# Sheet2_1.net
KiCad netlist of a schematic drawn in Altium Designer
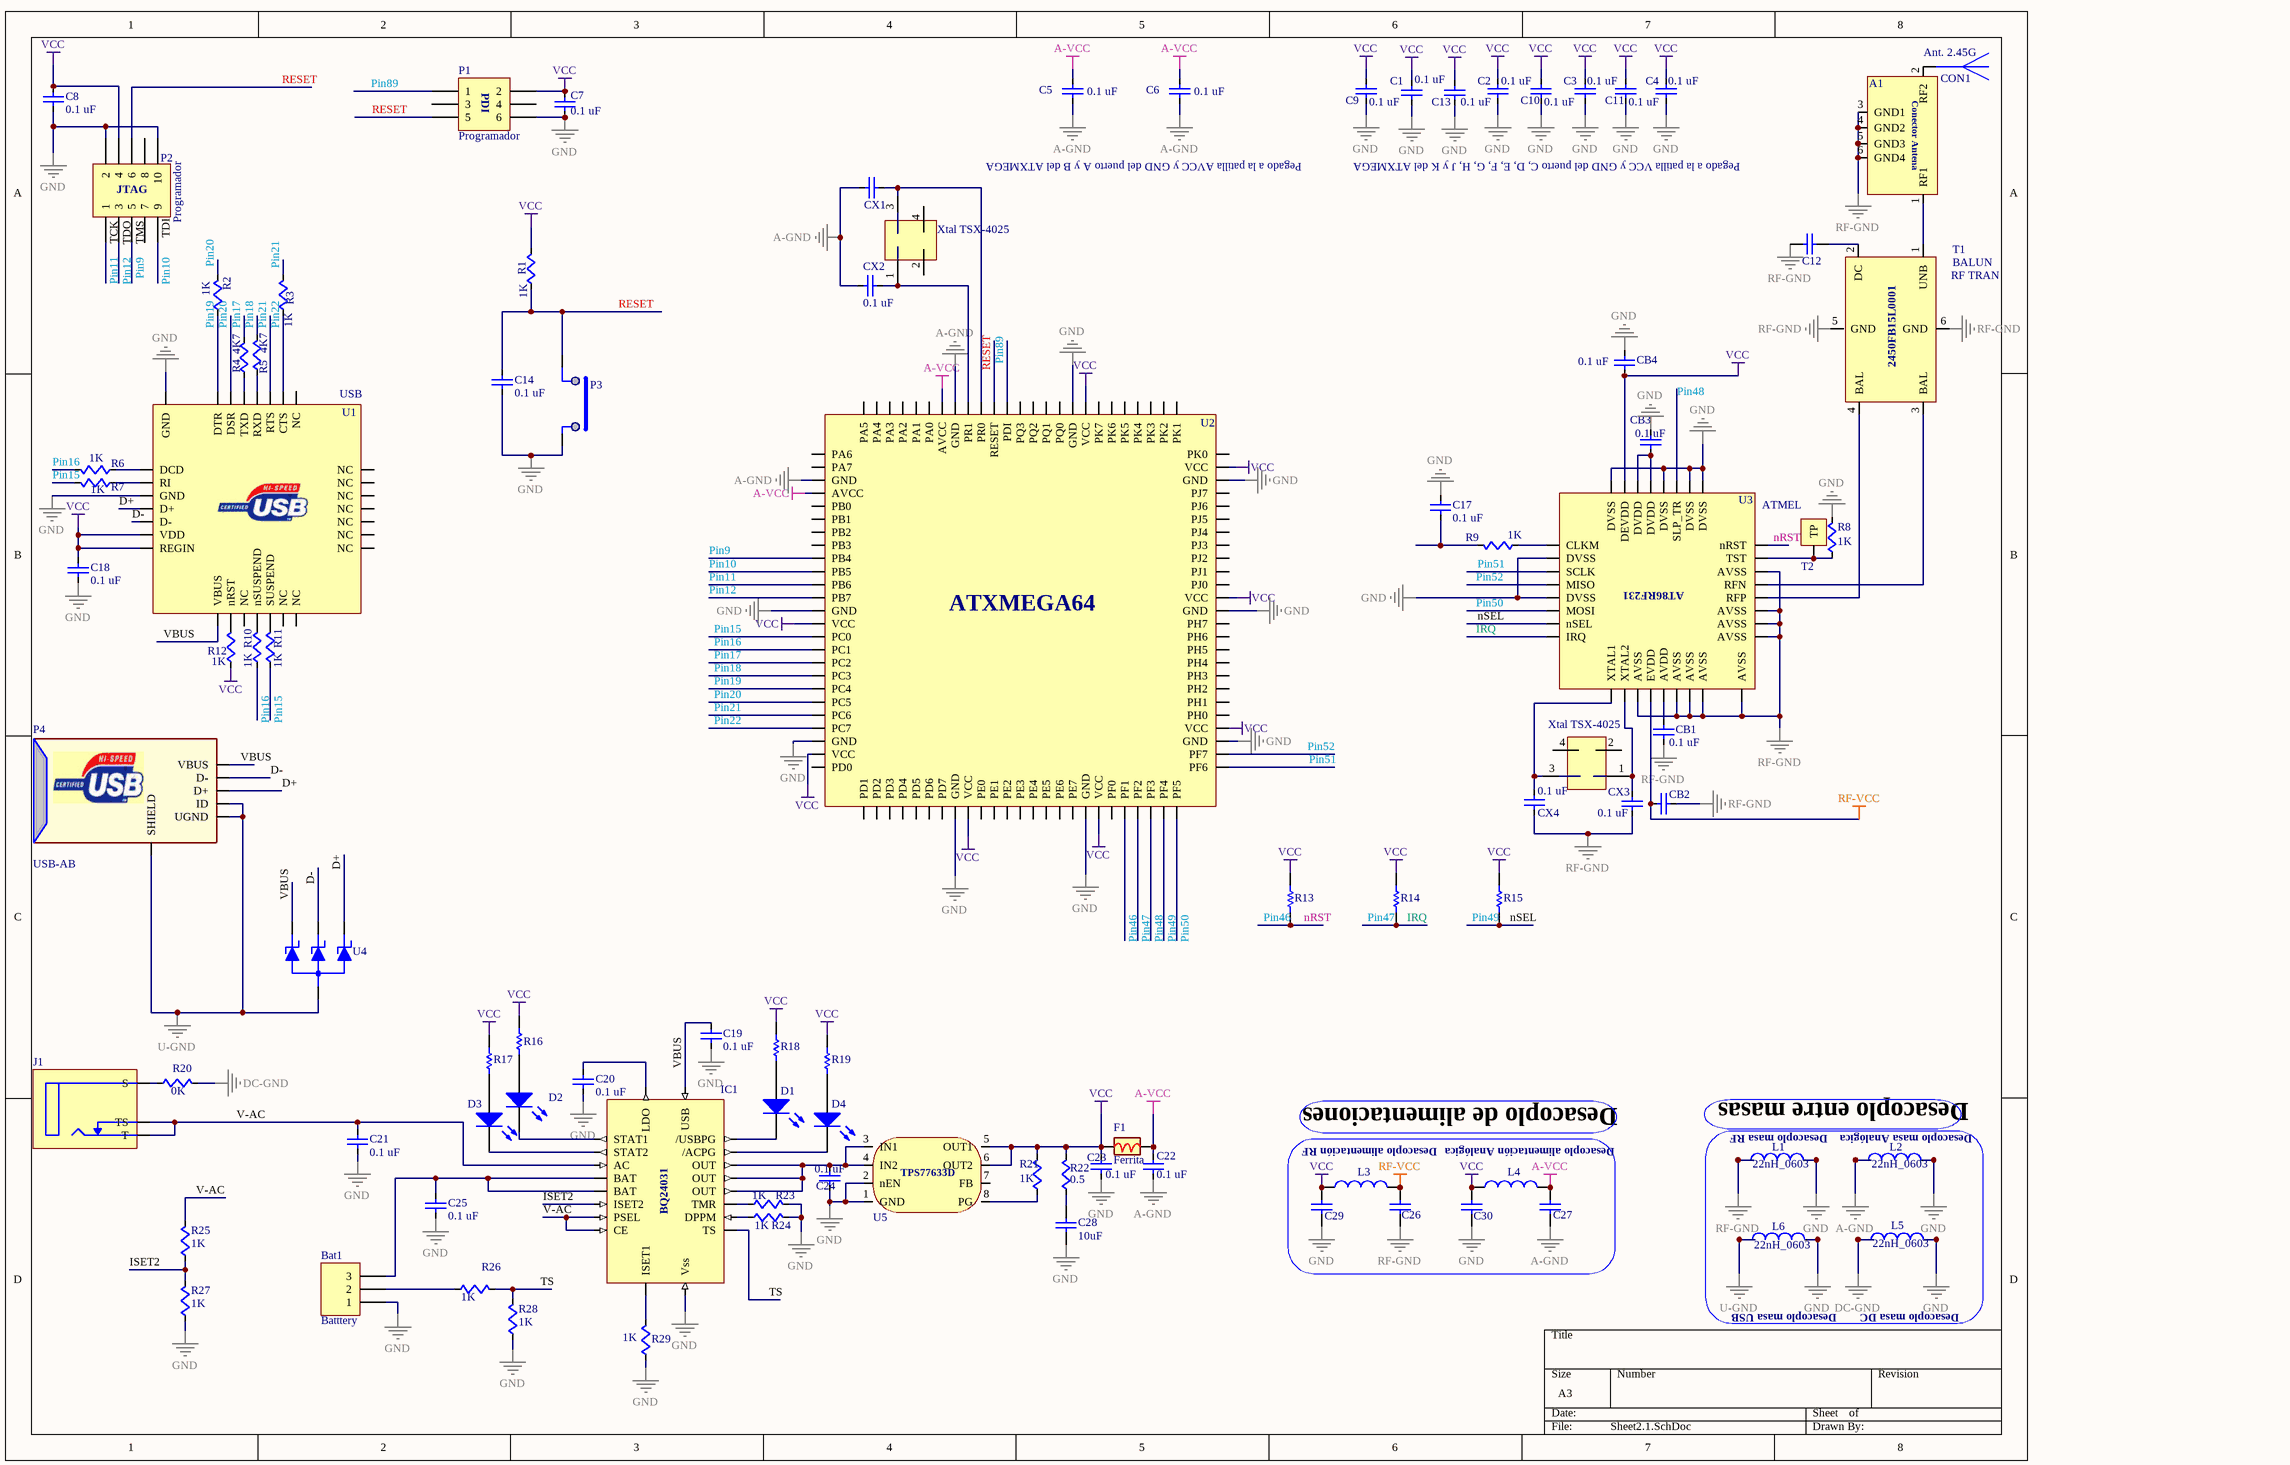
[diagram p0: Sheet2.1.SchDoc]

(export (version "E")
  (design (tool "Eeschema 10.0.6"))
  (components
    (comp (ref "A1")
      (value "Ant. 2.45G")
      (footprint "ANTENNA CHIP")
      (description "ANTENNA CHIP 2.4GHZ")
      (libsource (lib "Mia") (part "2450AT18A100"))
    )
    (comp (ref "Bat1")
      (value "Batttery")
      (footprint "HDR1X3")
      (description "Header, 3-Pin")
      (fields (field (name "PUBLISHER") "Altium Limited"))
      (libsource (lib "Mia") (part "Header 3"))
    )
    (comp (ref "C1")
      (value "C")
      (footprint "0402")
      (description "CONDENSADOR")
      (fields (field (name "VALOR") "0.1 uF"))
      (libsource (lib "Mia") (part "C"))
    )
    (comp (ref "C2")
      (value "C")
      (footprint "0402")
      (description "CONDENSADOR")
      (fields (field (name "VALOR") "0.1 uF"))
      (libsource (lib "Mia") (part "C"))
    )
    (comp (ref "C3")
      (value "C")
      (footprint "0402")
      (description "CONDENSADOR")
      (fields (field (name "VALOR") "0.1 uF"))
      (libsource (lib "Mia") (part "C"))
    )
    (comp (ref "C4")
      (value "C")
      (footprint "0402")
      (description "CONDENSADOR")
      (fields (field (name "VALOR") "0.1 uF"))
      (libsource (lib "Mia") (part "C"))
    )
    (comp (ref "C5")
      (value "C")
      (footprint "0402")
      (description "CONDENSADOR")
      (fields (field (name "VALOR") "0.1 uF"))
      (libsource (lib "Mia") (part "C"))
    )
    (comp (ref "C6")
      (value "C")
      (footprint "0402")
      (description "CONDENSADOR")
      (fields (field (name "VALOR") "0.1 uF"))
      (libsource (lib "Mia") (part "C"))
    )
    (comp (ref "C7")
      (value "C")
      (footprint "0402")
      (description "CONDENSADOR")
      (fields (field (name "VALOR") "0.1 uF"))
      (libsource (lib "Mia") (part "C"))
    )
    (comp (ref "C8")
      (value "C")
      (footprint "0402")
      (description "CONDENSADOR")
      (fields (field (name "VALOR") "0.1 uF"))
      (libsource (lib "Mia") (part "C"))
    )
    (comp (ref "C9")
      (value "C")
      (footprint "0402")
      (description "CONDENSADOR")
      (fields (field (name "VALOR") "0.1 uF"))
      (libsource (lib "Mia") (part "C"))
    )
    (comp (ref "C10")
      (value "C")
      (footprint "0402")
      (description "CONDENSADOR")
      (fields (field (name "VALOR") "0.1 uF"))
      (libsource (lib "Mia") (part "C"))
    )
    (comp (ref "C11")
      (value "C")
      (footprint "0402")
      (description "CONDENSADOR")
      (fields (field (name "VALOR") "0.1 uF"))
      (libsource (lib "Mia") (part "C"))
    )
    (comp (ref "C12")
      (value "22pF_0402")
      (footprint "0402")
      (description "CAP CER 56PF 50V 5% C0G 0402")
      (libsource (lib "Mia") (part "56pF_0402"))
    )
    (comp (ref "C13")
      (value "C")
      (footprint "0402")
      (description "CONDENSADOR")
      (fields (field (name "VALOR") "0.1 uF"))
      (libsource (lib "Mia") (part "C"))
    )
    (comp (ref "C14")
      (value "C")
      (footprint "0402")
      (description "CONDENSADOR")
      (fields (field (name "VALOR") "0.1 uF"))
      (libsource (lib "Mia") (part "C"))
    )
    (comp (ref "C17")
      (value "C")
      (footprint "0402")
      (description "CONDENSADOR")
      (fields (field (name "VALOR") "0.1 uF"))
      (libsource (lib "Mia") (part "C"))
    )
    (comp (ref "C18")
      (value "C")
      (footprint "0402")
      (description "CONDENSADOR")
      (fields (field (name "VALOR") "0.1 uF"))
      (libsource (lib "Mia") (part "C"))
    )
    (comp (ref "C19")
      (value "C")
      (footprint "0402")
      (description "CONDENSADOR")
      (fields (field (name "VALOR") "0.1 uF"))
      (libsource (lib "Mia") (part "C"))
    )
    (comp (ref "C20")
      (value "C")
      (footprint "0402")
      (description "CONDENSADOR")
      (fields (field (name "VALOR") "0.1 uF"))
      (libsource (lib "Mia") (part "C"))
    )
    (comp (ref "C21")
      (value "C")
      (footprint "0402")
      (description "CONDENSADOR")
      (fields (field (name "VALOR") "0.1 uF"))
      (libsource (lib "Mia") (part "C"))
    )
    (comp (ref "C22")
      (value "C")
      (footprint "0402")
      (description "CONDENSADOR")
      (fields (field (name "VALOR") "0.1 uF"))
      (libsource (lib "Mia") (part "C"))
    )
    (comp (ref "C23")
      (value "C")
      (footprint "0402")
      (description "CONDENSADOR")
      (fields (field (name "VALOR") "0.1 uF"))
      (libsource (lib "Mia") (part "C"))
    )
    (comp (ref "C24")
      (value "C")
      (footprint "0402")
      (description "CONDENSADOR")
      (fields (field (name "VALOR") "0.1 uF"))
      (libsource (lib "Mia") (part "C"))
    )
    (comp (ref "C25")
      (value "C")
      (footprint "0402")
      (description "CONDENSADOR")
      (fields (field (name "VALOR") "0.1 uF"))
      (libsource (lib "Mia") (part "C"))
    )
    (comp (ref "C26")
      (value "100nF_0805")
      (footprint "0805")
      (description "CAP CER 100PF 630V X7R 0805")
      (libsource (lib "Mia") (part "100nF_0805"))
    )
    (comp (ref "C27")
      (value "100nF_0805")
      (footprint "0805")
      (description "CAP CER 100PF 630V X7R 0805")
      (libsource (lib "Mia") (part "100nF_0805"))
    )
    (comp (ref "C28")
      (value "10uF")
      (footprint "0805")
      (description "CAP CER 10UF 10V Y5V 0805")
      (libsource (lib "Mia") (part "10uF_0805"))
    )
    (comp (ref "C29")
      (value "100nF_0805")
      (footprint "0805")
      (description "CAP CER 100PF 630V X7R 0805")
      (libsource (lib "Mia") (part "100nF_0805"))
    )
    (comp (ref "C30")
      (value "100nF_0805")
      (footprint "0805")
      (description "CAP CER 100PF 630V X7R 0805")
      (libsource (lib "Mia") (part "100nF_0805"))
    )
    (comp (ref "CB1")
      (value "C")
      (footprint "0402")
      (description "CONDENSADOR")
      (fields (field (name "VALOR") "0.1 uF"))
      (libsource (lib "Mia") (part "C"))
    )
    (comp (ref "CB2")
      (value "C")
      (footprint "0402")
      (description "CONDENSADOR")
      (fields (field (name "VALOR") "0.1 uF"))
      (libsource (lib "Mia") (part "C"))
    )
    (comp (ref "CB3")
      (value "C")
      (footprint "0402")
      (description "CONDENSADOR")
      (fields (field (name "VALOR") "0.1 uF"))
      (libsource (lib "Mia") (part "C"))
    )
    (comp (ref "CB4")
      (value "C")
      (footprint "0402")
      (description "CONDENSADOR")
      (fields (field (name "VALOR") "0.1 uF"))
      (libsource (lib "Mia") (part "C"))
    )
    (comp (ref "CON1")
      (value "Conector Antena")
      (footprint "MM8430-2600_Coaxial Connectors")
      (description "CONN MW COAXIAL WITH SWITCH")
      (libsource (lib "Mia") (part "CON ANT-MM8430-2600RA1"))
    )
    (comp (ref "CX1")
      (value "C")
      (footprint "0402")
      (description "CONDENSADOR")
      (libsource (lib "Mia") (part "C"))
    )
    (comp (ref "CX2")
      (value "C")
      (footprint "0402")
      (description "CONDENSADOR")
      (fields (field (name "VALOR") "0.1 uF"))
      (libsource (lib "Mia") (part "C"))
    )
    (comp (ref "CX3")
      (value "C")
      (footprint "0402")
      (description "CONDENSADOR")
      (fields (field (name "VALOR") "0.1 uF"))
      (libsource (lib "Mia") (part "C"))
    )
    (comp (ref "CX4")
      (value "C")
      (footprint "0402")
      (description "CONDENSADOR")
      (libsource (lib "Mia") (part "C"))
    )
    (comp (ref "D1")
      (value "Diodo Led")
      (footprint "Diode Led")
      (description "Typical INFRARED GaAs LED")
      (libsource (lib "Mia") (part "LTST-C230CKT"))
    )
    (comp (ref "D2")
      (value "Diodo Led")
      (footprint "Diode Led")
      (description "Typical INFRARED GaAs LED")
      (libsource (lib "Mia") (part "LTST-C230CKT"))
    )
    (comp (ref "D3")
      (value "Diodo Led")
      (footprint "Diode Led")
      (description "Typical INFRARED GaAs LED")
      (libsource (lib "Mia") (part "LTST-C230CKT"))
    )
    (comp (ref "D4")
      (value "Diodo Led")
      (footprint "Diode Led")
      (description "Typical INFRARED GaAs LED")
      (libsource (lib "Mia") (part "LTST-C230CKT"))
    )
    (comp (ref "F1")
      (value "Ferrita")
      (footprint "0603")
      (description "Chip Ferrite Beads")
      (libsource (lib "Mia") (part "BLM21AH102SN1"))
    )
    (comp (ref "IC1")
      (value "BQ24031")
      (footprint "BQ24031")
      (description "IC PWR MANAGEMENT SYSTEM 20-QFN")
      (libsource (lib "Mia") (part "BQ24031"))
    )
    (comp (ref "J1")
      (value "CAMSHOT")
      (footprint "MJ-2509N")
      (description "CONN MONO JACK 2.5MM PCB MNT")
      (libsource (lib "*") (part "MJ-2509N_1"))
    )
    (comp (ref "L1")
      (value "22nH_0603")
      (footprint "0603")
      (description "CER INDUCTOR 22NH 0603")
      (libsource (lib "Mia") (part "22nH_0603"))
    )
    (comp (ref "L2")
      (value "22nH_0603")
      (footprint "0603")
      (description "CER INDUCTOR 22NH 0603")
      (libsource (lib "Mia") (part "22nH_0603"))
    )
    (comp (ref "L3")
      (value "22nH_0603")
      (footprint "0603")
      (description "CER INDUCTOR 22NH 0603")
      (libsource (lib "Mia") (part "22nH_0603"))
    )
    (comp (ref "L4")
      (value "22nH_0603")
      (footprint "0603")
      (description "CER INDUCTOR 22NH 0603")
      (libsource (lib "Mia") (part "22nH_0603"))
    )
    (comp (ref "L5")
      (value "22nH_0603")
      (footprint "0603")
      (description "CER INDUCTOR 22NH 0603")
      (libsource (lib "Mia") (part "22nH_0603"))
    )
    (comp (ref "L6")
      (value "22nH_0603")
      (footprint "0603")
      (description "CER INDUCTOR 22NH 0603")
      (libsource (lib "Mia") (part "22nH_0603"))
    )
    (comp (ref "P1")
      (value "Programador")
      (footprint "HDR2X3")
      (description "Header, 3-Pin, Dual row")
      (fields (field (name "PUBLISHER") "Altium Limited"))
      (libsource (lib "Mia") (part "Header 3X2"))
    )
    (comp (ref "P2")
      (value "Programador")
      (footprint "HDR2X5")
      (description "Header, 5-Pin, Dual row")
      (fields (field (name "PUBLISHER") "Altium Limited"))
      (libsource (lib "Mia") (part "Header 5X2"))
    )
    (comp (ref "P3")
      (value "Pulsador")
      (footprint "PUSH-BUTTON-W")
      (description "SWITCH TACT 6X3.5MM H=4.3MM 180G")
      (libsource (lib "Mia") (part "PUSHBUTTON"))
    )
    (comp (ref "P4")
      (value "USB-AB")
      (footprint "USB-MINI-AB-SMT")
      (description "CONN RECEPT USB 5POS RT ANG SMD")
      (libsource (lib "Mia") (part "WM1722"))
    )
    (comp (ref "R1")
      (value "1K")
      (footprint "0603")
      (description "RESISTENCIA 0402 SMD")
      (fields (field (name "Comment") "R 0402"))
      (libsource (lib "Mia") (part "R 0402"))
    )
    (comp (ref "R2")
      (value "1K")
      (footprint "0603")
      (description "RESISTENCIA 0402 SMD")
      (fields (field (name "Comment") "R 0402"))
      (libsource (lib "Mia") (part "R 0402"))
    )
    (comp (ref "R3")
      (value "1K")
      (footprint "0603")
      (description "RESISTENCIA 0402 SMD")
      (fields (field (name "Comment") "R 0402"))
      (libsource (lib "Mia") (part "R 0402"))
    )
    (comp (ref "R4")
      (value "4K7")
      (footprint "0603")
      (description "RESISTENCIA 0402 SMD")
      (fields (field (name "Comment") "R 0402"))
      (libsource (lib "Mia") (part "R 0402"))
    )
    (comp (ref "R5")
      (value "4K7")
      (footprint "0603")
      (description "RESISTENCIA 0402 SMD")
      (fields (field (name "Comment") "R 0402"))
      (libsource (lib "Mia") (part "R 0402"))
    )
    (comp (ref "R6")
      (value "1K")
      (footprint "0603")
      (description "RESISTENCIA 0402 SMD")
      (fields (field (name "Comment") "R 0402"))
      (libsource (lib "Mia") (part "R 0402"))
    )
    (comp (ref "R7")
      (value "1K")
      (footprint "0603")
      (description "RESISTENCIA 0402 SMD")
      (fields (field (name "Comment") "R 0402"))
      (libsource (lib "Mia") (part "R 0402"))
    )
    (comp (ref "R8")
      (value "1K")
      (footprint "0603")
      (description "RESISTENCIA 0402 SMD")
      (fields (field (name "Comment") "R 0402"))
      (libsource (lib "Mia") (part "R 0402"))
    )
    (comp (ref "R9")
      (value "1K")
      (footprint "0603")
      (description "RESISTENCIA 0402 SMD")
      (fields (field (name "Comment") "R 0402"))
      (libsource (lib "Mia") (part "R 0402"))
    )
    (comp (ref "R10")
      (value "1K")
      (footprint "0603")
      (description "RESISTENCIA 0402 SMD")
      (fields (field (name "Comment") "R 0402"))
      (libsource (lib "Mia") (part "R 0402"))
    )
    (comp (ref "R11")
      (value "1K")
      (footprint "0603")
      (description "RESISTENCIA 0402 SMD")
      (fields (field (name "Comment") "R 0402"))
      (libsource (lib "Mia") (part "R 0402"))
    )
    (comp (ref "R12")
      (value "1K")
      (footprint "0603")
      (description "RESISTENCIA 0402 SMD")
      (fields (field (name "Comment") "R 0402"))
      (libsource (lib "Mia") (part "R 0402"))
    )
    (comp (ref "R13")
      (value "16.9kohm-0805")
      (footprint "0805")
      (description "RES 16.9K OHM 1/8W 1% 0805 SMD")
      (libsource (lib "Mia") (part "16.9kohm-0805"))
    )
    (comp (ref "R14")
      (value "16.9kohm-0805")
      (footprint "0805")
      (description "RES 16.9K OHM 1/8W 1% 0805 SMD")
      (libsource (lib "Mia") (part "16.9kohm-0805"))
    )
    (comp (ref "R15")
      (value "16.9kohm-0805")
      (footprint "0805")
      (description "RES 16.9K OHM 1/8W 1% 0805 SMD")
      (libsource (lib "Mia") (part "16.9kohm-0805"))
    )
    (comp (ref "R16")
      (value "16.9kohm-0805")
      (footprint "0805")
      (description "RES 16.9K OHM 1/8W 1% 0805 SMD")
      (libsource (lib "Mia") (part "16.9kohm-0805"))
    )
    (comp (ref "R17")
      (value "16.9kohm-0805")
      (footprint "0805")
      (description "RES 16.9K OHM 1/8W 1% 0805 SMD")
      (libsource (lib "Mia") (part "16.9kohm-0805"))
    )
    (comp (ref "R18")
      (value "16.9kohm-0805")
      (footprint "0805")
      (description "RES 16.9K OHM 1/8W 1% 0805 SMD")
      (libsource (lib "Mia") (part "16.9kohm-0805"))
    )
    (comp (ref "R19")
      (value "16.9kohm-0805")
      (footprint "0805")
      (description "RES 16.9K OHM 1/8W 1% 0805 SMD")
      (libsource (lib "Mia") (part "16.9kohm-0805"))
    )
    (comp (ref "R20")
      (value "0K")
      (footprint "0603")
      (description "RESISTENCIA 0402 SMD")
      (fields (field (name "Comment") "R 0402"))
      (libsource (lib "Mia") (part "R 0402"))
    )
    (comp (ref "R21")
      (value "1K")
      (footprint "0603")
      (description "RESISTENCIA 0402 SMD")
      (fields (field (name "Comment") "R 0402"))
      (libsource (lib "Mia") (part "R 0402"))
    )
    (comp (ref "R22")
      (value "0.5")
      (footprint "0603")
      (description "RESISTENCIA 0402 SMD")
      (fields (field (name "Comment") "R 0402"))
      (libsource (lib "Mia") (part "R 0402"))
    )
    (comp (ref "R23")
      (value "1K")
      (footprint "0603")
      (description "RESISTENCIA 0402 SMD")
      (fields (field (name "Comment") "R 0402"))
      (libsource (lib "Mia") (part "R 0402"))
    )
    (comp (ref "R24")
      (value "1K")
      (footprint "0603")
      (description "RESISTENCIA 0402 SMD")
      (fields (field (name "Comment") "R 0402"))
      (libsource (lib "Mia") (part "R 0402"))
    )
    (comp (ref "R25")
      (value "1K")
      (footprint "0603")
      (description "RESISTENCIA 0402 SMD")
      (fields (field (name "Comment") "R 0402"))
      (libsource (lib "Mia") (part "R 0402"))
    )
    (comp (ref "R26")
      (value "1K")
      (footprint "0603")
      (description "RESISTENCIA 0402 SMD")
      (fields (field (name "Comment") "R 0402"))
      (libsource (lib "Mia") (part "R 0402"))
    )
    (comp (ref "R27")
      (value "1K")
      (footprint "0603")
      (description "RESISTENCIA 0402 SMD")
      (fields (field (name "Comment") "R 0402"))
      (libsource (lib "Mia") (part "R 0402"))
    )
    (comp (ref "R28")
      (value "1K")
      (footprint "0603")
      (description "RESISTENCIA 0402 SMD")
      (fields (field (name "Comment") "R 0402"))
      (libsource (lib "Mia") (part "R 0402"))
    )
    (comp (ref "R29")
      (value "1K")
      (footprint "0603")
      (description "RESISTENCIA 0402 SMD")
      (fields (field (name "Comment") "R 0402"))
      (libsource (lib "Mia") (part "R 0402"))
    )
    (comp (ref "T1")
      (value "BALUN")
      (footprint "BALUN")
      (description "FILTER BALUN CER CHIP 2.4GHZ")
      (libsource (lib "Mia") (part "2450FB39B100E"))
    )
    (comp (ref "T2")
      (value "TESTPOINT")
      (footprint "TESTPOINT")
      (description "Punto de Test")
      (libsource (lib "Mia") (part "TESTPOINT"))
    )
    (comp (ref "U1")
      (value "USB")
      (footprint "QFN28_5X5")
      (description "IC USB-TO-UART BRIDGE 28MLP")
      (libsource (lib "Mia") (part "CP2102"))
    )
    (comp (ref "U2")
      (value "XMEGA")
      (footprint "Quad100")
      (description "MCU AVR 64K FLASH 1.6V 100-TQFP")
      (libsource (lib "Mia") (part "ATXMEGA64A1"))
    )
    (comp (ref "U3")
      (value "RF TRAN")
      (footprint "QFN32_50")
      (description "IC TXRX ZIGBEE/802.15.4 32QFN")
      (fields (field (name "FABRICANTE") "ATMEL"))
      (libsource (lib "Mia") (part "AT86RF231"))
    )
    (comp (ref "U4")
      (value "TVS")
      (footprint "SOT-143")
      (description "TVS AVAL DIODE ARRAY 3 CH SOT143")
      (libsource (lib "Mia") (part "SP0503BAHTG"))
    )
    (comp (ref "U5")
      (value "TPS77633D")
      (footprint "TPS77633D")
      (description "IC 3.3V 500MA LDO REG 8-SOIC")
      (libsource (lib "Mia") (part "TPS77633D"))
    )
    (comp (ref "Xtal1")
      (value "Xtal TSX-4025")
      (footprint "TSX-4025")
      (description "Cristal 16Mhz")
      (libsource (lib "Mia") (part "Xtal TSX-4025"))
    )
    (comp (ref "Xtal2")
      (value "Xtal TSX-4025")
      (footprint "TSX-4025")
      (description "Cristal 16Mhz")
      (libsource (lib "") (part "Xtal TSX-4025_1"))
    )
  )
  (nets
    (net (code "1") (name "/D+") (class "Default")
      (node (ref "P4") (pin "D+") (pinfunction "D+_D+") (pintype "passive"))
      (node (ref "U1") (pin "4") (pinfunction "D+_4") (pintype "passive"))
      (node (ref "U4") (pin "2") (pinfunction "C_2") (pintype "passive"))
    )
    (net (code "2") (name "/D-") (class "Default")
      (node (ref "P4") (pin "D-") (pinfunction "D-_D-") (pintype "passive"))
      (node (ref "U1") (pin "5") (pinfunction "D-_5") (pintype "passive"))
      (node (ref "U4") (pin "3") (pinfunction "C_3") (pintype "passive"))
    )
    (net (code "3") (name "/IRQ") (class "Default")
      (node (ref "R14") (pin "1") (pinfunction "1_1") (pintype "passive"))
      (node (ref "U2") (pin "47") (pinfunction "PF2_47") (pintype "passive"))
      (node (ref "U3") (pin "24") (pinfunction "IRQ_24") (pintype "passive"))
    )
    (net (code "4") (name "/ISET2") (class "Default")
      (node (ref "IC1") (pin "7") (pinfunction "ISET2_7") (pintype "input"))
      (node (ref "R25") (pin "1") (pinfunction "1_1") (pintype "passive"))
      (node (ref "R27") (pin "2") (pinfunction "2_2") (pintype "passive"))
    )
    (net (code "5") (name "/Pin9") (class "Default")
      (node (ref "P2") (pin "5") (pinfunction "5_5") (pintype "passive"))
      (node (ref "U2") (pin "9") (pinfunction "PB4_9") (pintype "passive"))
    )
    (net (code "6") (name "/Pin10") (class "Default")
      (node (ref "P2") (pin "9") (pinfunction "9_9") (pintype "passive"))
      (node (ref "U2") (pin "10") (pinfunction "PB5_10") (pintype "passive"))
    )
    (net (code "7") (name "/Pin11") (class "Default")
      (node (ref "P2") (pin "1") (pinfunction "1_1") (pintype "passive"))
      (node (ref "U2") (pin "11") (pinfunction "PB6_11") (pintype "passive"))
    )
    (net (code "8") (name "/Pin12") (class "Default")
      (node (ref "P2") (pin "3") (pinfunction "3_3") (pintype "passive"))
      (node (ref "U2") (pin "12") (pinfunction "PB7_12") (pintype "passive"))
    )
    (net (code "9") (name "/Pin15") (class "Default")
      (node (ref "R11") (pin "1") (pinfunction "1_1") (pintype "passive"))
      (node (ref "R7") (pin "2") (pinfunction "2_2") (pintype "passive"))
      (node (ref "U2") (pin "15") (pinfunction "PC0_15") (pintype "passive"))
    )
    (net (code "10") (name "/Pin16") (class "Default")
      (node (ref "R10") (pin "1") (pinfunction "1_1") (pintype "passive"))
      (node (ref "R6") (pin "2") (pinfunction "2_2") (pintype "passive"))
      (node (ref "U2") (pin "16") (pinfunction "PC1_16") (pintype "passive"))
    )
    (net (code "11") (name "/Pin17") (class "Default")
      (node (ref "R4") (pin "2") (pinfunction "2_2") (pintype "passive"))
      (node (ref "U2") (pin "17") (pinfunction "PC2_17") (pintype "passive"))
    )
    (net (code "12") (name "/Pin18") (class "Default")
      (node (ref "R5") (pin "2") (pinfunction "2_2") (pintype "passive"))
      (node (ref "U2") (pin "18") (pinfunction "PC3_18") (pintype "passive"))
    )
    (net (code "13") (name "/Pin19") (class "Default")
      (node (ref "R2") (pin "1") (pinfunction "1_1") (pintype "passive"))
      (node (ref "U1") (pin "28") (pinfunction "DTR_28") (pintype "passive"))
      (node (ref "U2") (pin "19") (pinfunction "PC4_19") (pintype "passive"))
    )
    (net (code "14") (name "/Pin20") (class "Default")
      (node (ref "R2") (pin "2") (pinfunction "2_2") (pintype "passive"))
      (node (ref "U1") (pin "27") (pinfunction "DSR_27") (pintype "passive"))
      (node (ref "U2") (pin "20") (pinfunction "PC5_20") (pintype "passive"))
    )
    (net (code "15") (name "/Pin21") (class "Default")
      (node (ref "R3") (pin "2") (pinfunction "2_2") (pintype "passive"))
      (node (ref "U1") (pin "24") (pinfunction "RTS_24") (pintype "passive"))
      (node (ref "U2") (pin "21") (pinfunction "PC6_21") (pintype "passive"))
    )
    (net (code "16") (name "/Pin22") (class "Default")
      (node (ref "R3") (pin "1") (pinfunction "1_1") (pintype "passive"))
      (node (ref "U1") (pin "23") (pinfunction "CTS_23") (pintype "passive"))
      (node (ref "U2") (pin "22") (pinfunction "PC7_22") (pintype "passive"))
    )
    (net (code "17") (name "/Pin46") (class "Default")
      (node (ref "R13") (pin "1") (pinfunction "1_1") (pintype "passive"))
      (node (ref "U2") (pin "46") (pinfunction "PF1_46") (pintype "passive"))
      (node (ref "U3") (pin "8") (pinfunction "nRST_8") (pintype "passive"))
    )
    (net (code "18") (name "/Pin48") (class "Default")
      (node (ref "U2") (pin "48") (pinfunction "PF3_48") (pintype "passive"))
      (node (ref "U3") (pin "11") (pinfunction "SLP_TR_11") (pintype "passive"))
    )
    (net (code "19") (name "/Pin49") (class "Default")
      (node (ref "R15") (pin "1") (pinfunction "1_1") (pintype "passive"))
      (node (ref "U2") (pin "49") (pinfunction "PF4_49") (pintype "passive"))
      (node (ref "U3") (pin "23") (pinfunction "nSEL_23") (pintype "passive"))
    )
    (net (code "20") (name "/Pin50") (class "Default")
      (node (ref "U2") (pin "50") (pinfunction "PF5_50") (pintype "passive"))
      (node (ref "U3") (pin "22") (pinfunction "MOSI_22") (pintype "passive"))
    )
    (net (code "21") (name "/Pin51") (class "Default")
      (node (ref "U2") (pin "51") (pinfunction "PF6_51") (pintype "passive"))
      (node (ref "U3") (pin "19") (pinfunction "SCLK_19") (pintype "passive"))
    )
    (net (code "22") (name "/Pin52") (class "Default")
      (node (ref "U2") (pin "52") (pinfunction "PF7_52") (pintype "passive"))
      (node (ref "U3") (pin "20") (pinfunction "MISO_20") (pintype "passive"))
    )
    (net (code "23") (name "/Pin89") (class "Default")
      (node (ref "P1") (pin "1") (pinfunction "1_1") (pintype "passive"))
      (node (ref "U2") (pin "89") (pinfunction "PDI_89") (pintype "passive"))
    )
    (net (code "24") (name "/RESET") (class "Default")
      (node (ref "C14") (pin "1") (pinfunction "1_1") (pintype "passive"))
      (node (ref "P1") (pin "5") (pinfunction "5_5") (pintype "passive"))
      (node (ref "P2") (pin "6") (pinfunction "6_6") (pintype "passive"))
      (node (ref "P3") (pin "1") (pinfunction "1_1") (pintype "passive"))
      (node (ref "R1") (pin "1") (pinfunction "1_1") (pintype "passive"))
      (node (ref "U2") (pin "90") (pinfunction "RESET_90") (pintype "passive"))
    )
    (net (code "29") (name "/TS") (class "Default")
      (node (ref "IC1") (pin "12") (pinfunction "TS_12") (pintype "bidirectional"))
      (node (ref "R26") (pin "2") (pinfunction "2_2") (pintype "passive"))
      (node (ref "R28") (pin "2") (pinfunction "2_2") (pintype "passive"))
    )
    (net (code "30") (name "/V-AC") (class "Default")
      (node (ref "C21") (pin "1") (pinfunction "1_1") (pintype "passive"))
      (node (ref "IC1") (pin "4") (pinfunction "AC_4") (pintype "input"))
      (node (ref "IC1") (pin "8") (pinfunction "PSEL_8") (pintype "input"))
      (node (ref "IC1") (pin "9") (pinfunction "CE_9") (pintype "input"))
      (node (ref "J1") (pin "2") (pinfunction "T_2") (pintype "passive"))
      (node (ref "J1") (pin "3") (pinfunction "TS_3") (pintype "passive"))
      (node (ref "R25") (pin "2") (pinfunction "2_2") (pintype "passive"))
    )
    (net (code "31") (name "/VBUS") (class "Default")
      (node (ref "C19") (pin "1") (pinfunction "1_1") (pintype "passive"))
      (node (ref "IC1") (pin "20") (pinfunction "USB_20") (pintype "input"))
      (node (ref "P4") (pin "VBUS") (pinfunction "VBUS_VBUS") (pintype "passive"))
      (node (ref "U1") (pin "8") (pinfunction "VBUS_8") (pintype "passive"))
      (node (ref "U4") (pin "4") (pinfunction "C_4") (pintype "passive"))
    )
    (net (code "32") (name "A-GND") (class "Default")
      (node (ref "C22") (pin "2") (pinfunction "2_2") (pintype "passive"))
      (node (ref "C27") (pin "1") (pinfunction "1_1") (pintype "passive"))
      (node (ref "C5") (pin "2") (pinfunction "2_2") (pintype "passive"))
      (node (ref "C6") (pin "2") (pinfunction "2_2") (pintype "passive"))
      (node (ref "CX1") (pin "1") (pinfunction "1_1") (pintype "passive"))
      (node (ref "CX2") (pin "1") (pinfunction "1_1") (pintype "passive"))
      (node (ref "L2") (pin "1") (pinfunction "1_1") (pintype "passive"))
      (node (ref "U2") (pin "3") (pinfunction "GND_3") (pintype "passive"))
      (node (ref "U2") (pin "93") (pinfunction "GND_93") (pintype "passive"))
    )
    (net (code "33") (name "A-VCC") (class "Default")
      (node (ref "C22") (pin "1") (pinfunction "1_1") (pintype "passive"))
      (node (ref "C27") (pin "2") (pinfunction "2_2") (pintype "passive"))
      (node (ref "C5") (pin "1") (pinfunction "1_1") (pintype "passive"))
      (node (ref "C6") (pin "1") (pinfunction "1_1") (pintype "passive"))
      (node (ref "F1") (pin "2") (pinfunction "Y_2") (pintype "passive"))
      (node (ref "L4") (pin "2") (pinfunction "2_2") (pintype "passive"))
      (node (ref "U2") (pin "4") (pinfunction "AVCC_4") (pintype "passive"))
      (node (ref "U2") (pin "94") (pinfunction "AVCC_94") (pintype "passive"))
    )
    (net (code "34") (name "DC-GND") (class "Default")
      (node (ref "L5") (pin "1") (pinfunction "1_1") (pintype "passive"))
      (node (ref "R20") (pin "2") (pinfunction "2_2") (pintype "passive"))
    )
    (net (code "35") (name "GND") (class "Default")
      (node (ref "Bat1") (pin "1") (pinfunction "1_1") (pintype "passive"))
      (node (ref "C1") (pin "2") (pinfunction "2_2") (pintype "passive"))
      (node (ref "C10") (pin "2") (pinfunction "2_2") (pintype "passive"))
      (node (ref "C11") (pin "2") (pinfunction "2_2") (pintype "passive"))
      (node (ref "C13") (pin "2") (pinfunction "2_2") (pintype "passive"))
      (node (ref "C14") (pin "2") (pinfunction "2_2") (pintype "passive"))
      (node (ref "C17") (pin "1") (pinfunction "1_1") (pintype "passive"))
      (node (ref "C18") (pin "2") (pinfunction "2_2") (pintype "passive"))
      (node (ref "C19") (pin "2") (pinfunction "2_2") (pintype "passive"))
      (node (ref "C2") (pin "2") (pinfunction "2_2") (pintype "passive"))
      (node (ref "C20") (pin "2") (pinfunction "2_2") (pintype "passive"))
      (node (ref "C21") (pin "2") (pinfunction "2_2") (pintype "passive"))
      (node (ref "C23") (pin "2") (pinfunction "2_2") (pintype "passive"))
      (node (ref "C24") (pin "2") (pinfunction "2_2") (pintype "passive"))
      (node (ref "C25") (pin "2") (pinfunction "2_2") (pintype "passive"))
      (node (ref "C28") (pin "1") (pinfunction "1_1") (pintype "passive"))
      (node (ref "C29") (pin "1") (pinfunction "1_1") (pintype "passive"))
      (node (ref "C3") (pin "2") (pinfunction "2_2") (pintype "passive"))
      (node (ref "C30") (pin "1") (pinfunction "1_1") (pintype "passive"))
      (node (ref "C4") (pin "2") (pinfunction "2_2") (pintype "passive"))
      (node (ref "C7") (pin "2") (pinfunction "2_2") (pintype "passive"))
      (node (ref "C8") (pin "2") (pinfunction "2_2") (pintype "passive"))
      (node (ref "C9") (pin "2") (pinfunction "2_2") (pintype "passive"))
      (node (ref "CB3") (pin "1") (pinfunction "1_1") (pintype "passive"))
      (node (ref "CB4") (pin "2") (pinfunction "2_2") (pintype "passive"))
      (node (ref "IC1") (pin "11") (pinfunction "Vss_11") (pintype "input"))
      (node (ref "L1") (pin "2") (pinfunction "2_2") (pintype "passive"))
      (node (ref "L2") (pin "2") (pinfunction "2_2") (pintype "passive"))
      (node (ref "L5") (pin "2") (pinfunction "2_2") (pintype "passive"))
      (node (ref "L6") (pin "2") (pinfunction "2_2") (pintype "passive"))
      (node (ref "P1") (pin "6") (pinfunction "6_6") (pintype "passive"))
      (node (ref "P2") (pin "10") (pinfunction "10_10") (pintype "passive"))
      (node (ref "P2") (pin "2") (pinfunction "2_2") (pintype "passive"))
      (node (ref "P3") (pin "2") (pinfunction "2_2") (pintype "passive"))
      (node (ref "R23") (pin "2") (pinfunction "2_2") (pintype "passive"))
      (node (ref "R24") (pin "2") (pinfunction "2_2") (pintype "passive"))
      (node (ref "R27") (pin "1") (pinfunction "1_1") (pintype "passive"))
      (node (ref "R28") (pin "1") (pinfunction "1_1") (pintype "passive"))
      (node (ref "R29") (pin "1") (pinfunction "1_1") (pintype "passive"))
      (node (ref "R8") (pin "2") (pinfunction "2_2") (pintype "passive"))
      (node (ref "U1") (pin "0") (pinfunction "GND_0") (pintype "passive"))
      (node (ref "U1") (pin "3") (pinfunction "GND_3") (pintype "passive"))
      (node (ref "U2") (pin "13") (pinfunction "GND_13") (pintype "passive"))
      (node (ref "U2") (pin "23") (pinfunction "GND_23") (pintype "passive"))
      (node (ref "U2") (pin "33") (pinfunction "GND_33") (pintype "passive"))
      (node (ref "U2") (pin "43") (pinfunction "GND_43") (pintype "passive"))
      (node (ref "U2") (pin "53") (pinfunction "GND_53") (pintype "passive"))
      (node (ref "U2") (pin "63") (pinfunction "GND_63") (pintype "passive"))
      (node (ref "U2") (pin "73") (pinfunction "GND_73") (pintype "passive"))
      (node (ref "U2") (pin "84") (pinfunction "GND_84") (pintype "passive"))
      (node (ref "U3") (pin "10") (pinfunction "DVSS_10") (pintype "passive"))
      (node (ref "U3") (pin "12") (pinfunction "DVSS_12") (pintype "passive"))
      (node (ref "U3") (pin "16") (pinfunction "DVSS_16") (pintype "passive"))
      (node (ref "U3") (pin "18") (pinfunction "DVSS_18") (pintype "passive"))
      (node (ref "U3") (pin "21") (pinfunction "DVSS_21") (pintype "passive"))
      (node (ref "U3") (pin "9") (pinfunction "DVSS_9") (pintype "passive"))
      (node (ref "U5") (pin "1") (pinfunction "GND_1") (pintype "passive"))
      (node (ref "U5") (pin "2") (pinfunction "nEN_2") (pintype "passive"))
    )
    (net (code "36") (name "Net-(A1-OUT)") (class "Default")
      (node (ref "A1") (pin "1") (pinfunction "OUT_1") (pintype "passive"))
      (node (ref "CON1") (pin "2") (pinfunction "RF2_2") (pintype "passive"))
    )
    (net (code "37") (name "Net-(Bat1-Pad2)") (class "Default")
      (node (ref "Bat1") (pin "2") (pinfunction "2_2") (pintype "passive"))
      (node (ref "R26") (pin "1") (pinfunction "1_1") (pintype "passive"))
    )
    (net (code "38") (name "Net-(Bat1-Pad3)") (class "Default")
      (node (ref "Bat1") (pin "3") (pinfunction "3_3") (pintype "passive"))
      (node (ref "C25") (pin "1") (pinfunction "1_1") (pintype "passive"))
      (node (ref "IC1") (pin "5") (pinfunction "BAT_5") (pintype "bidirectional"))
      (node (ref "IC1") (pin "6") (pinfunction "BAT_6") (pintype "bidirectional"))
    )
    (net (code "39") (name "Net-(C17-Pad2)") (class "Default")
      (node (ref "C17") (pin "2") (pinfunction "2_2") (pintype "passive"))
      (node (ref "R9") (pin "2") (pinfunction "2_2") (pintype "passive"))
    )
    (net (code "40") (name "Net-(C28-Pad2)") (class "Default")
      (node (ref "C28") (pin "2") (pinfunction "2_2") (pintype "passive"))
      (node (ref "R22") (pin "1") (pinfunction "1_1") (pintype "passive"))
    )
    (net (code "41") (name "Net-(CB3-Pad2)") (class "Default")
      (node (ref "CB3") (pin "2") (pinfunction "2_2") (pintype "passive"))
      (node (ref "U3") (pin "13") (pinfunction "DVDD_13") (pintype "passive"))
      (node (ref "U3") (pin "14") (pinfunction "DVDD_14") (pintype "passive"))
    )
    (net (code "42") (name "Net-(CON1-RF1)") (class "Default")
      (node (ref "CON1") (pin "1") (pinfunction "RF1_1") (pintype "passive"))
      (node (ref "T1") (pin "1") (pinfunction "UNB_1") (pintype "passive"))
    )
    (net (code "43") (name "Net-(D1-A)") (class "Default")
      (node (ref "D1") (pin "1") (pinfunction "A_1") (pintype "passive"))
      (node (ref "R18") (pin "1") (pinfunction "1_1") (pintype "passive"))
    )
    (net (code "44") (name "Net-(D1-K)") (class "Default")
      (node (ref "D1") (pin "2") (pinfunction "K_2") (pintype "passive"))
      (node (ref "IC1") (pin "19") (pinfunction "/USBPG_19") (pintype "output"))
    )
    (net (code "45") (name "Net-(D2-A)") (class "Default")
      (node (ref "D2") (pin "1") (pinfunction "A_1") (pintype "passive"))
      (node (ref "R16") (pin "1") (pinfunction "1_1") (pintype "passive"))
    )
    (net (code "46") (name "Net-(D2-K)") (class "Default")
      (node (ref "D2") (pin "2") (pinfunction "K_2") (pintype "passive"))
      (node (ref "IC1") (pin "2") (pinfunction "STAT1_2") (pintype "output"))
    )
    (net (code "47") (name "Net-(D3-A)") (class "Default")
      (node (ref "D3") (pin "1") (pinfunction "A_1") (pintype "passive"))
      (node (ref "R17") (pin "1") (pinfunction "1_1") (pintype "passive"))
    )
    (net (code "48") (name "Net-(D3-K)") (class "Default")
      (node (ref "D3") (pin "2") (pinfunction "K_2") (pintype "passive"))
      (node (ref "IC1") (pin "3") (pinfunction "STAT2_3") (pintype "output"))
    )
    (net (code "49") (name "Net-(D4-A)") (class "Default")
      (node (ref "D4") (pin "1") (pinfunction "A_1") (pintype "passive"))
      (node (ref "R19") (pin "1") (pinfunction "1_1") (pintype "passive"))
    )
    (net (code "50") (name "Net-(D4-K)") (class "Default")
      (node (ref "D4") (pin "2") (pinfunction "K_2") (pintype "passive"))
      (node (ref "IC1") (pin "18") (pinfunction "/ACPG_18") (pintype "output"))
    )
    (net (code "51") (name "Net-(IC1-DPPM)") (class "Default")
      (node (ref "IC1") (pin "13") (pinfunction "DPPM_13") (pintype "input"))
      (node (ref "R23") (pin "1") (pinfunction "1_1") (pintype "passive"))
    )
    (net (code "52") (name "Net-(IC1-ISET1)") (class "Default")
      (node (ref "IC1") (pin "10") (pinfunction "ISET1_10") (pintype "bidirectional"))
      (node (ref "R29") (pin "2") (pinfunction "2_2") (pintype "passive"))
    )
    (net (code "53") (name "Net-(IC1-LDO)") (class "Default")
      (node (ref "C20") (pin "1") (pinfunction "1_1") (pintype "passive"))
      (node (ref "IC1") (pin "1") (pinfunction "LDO_1") (pintype "output"))
    )
    (net (code "54") (name "Net-(IC1-TMR)") (class "Default")
      (node (ref "IC1") (pin "14") (pinfunction "TMR_14") (pintype "bidirectional"))
      (node (ref "R24") (pin "1") (pinfunction "1_1") (pintype "passive"))
    )
    (net (code "55") (name "Net-(J1-S)") (class "Default")
      (node (ref "J1") (pin "1") (pinfunction "S_1") (pintype "passive"))
      (node (ref "R20") (pin "1") (pinfunction "1_1") (pintype "passive"))
    )
    (net (code "56") (name "Net-(T1-DC)") (class "Default")
      (node (ref "C12") (pin "2") (pinfunction "2_2") (pintype "passive"))
      (node (ref "T1") (pin "2") (pinfunction "DC_2") (pintype "passive"))
    )
    (net (code "57") (name "Net-(T2-TP)") (class "Default")
      (node (ref "R8") (pin "1") (pinfunction "1_1") (pintype "passive"))
      (node (ref "T2") (pin "1") (pinfunction "TP_1") (pintype "passive"))
      (node (ref "U3") (pin "7") (pinfunction "TST_7") (pintype "passive"))
    )
    (net (code "58") (name "Net-(U1-DCD)") (class "Default")
      (node (ref "R6") (pin "1") (pinfunction "1_1") (pintype "passive"))
      (node (ref "U1") (pin "1") (pinfunction "DCD_1") (pintype "passive"))
    )
    (net (code "59") (name "Net-(U1-RI)") (class "Default")
      (node (ref "R7") (pin "1") (pinfunction "1_1") (pintype "passive"))
      (node (ref "U1") (pin "2") (pinfunction "RI_2") (pintype "passive"))
    )
    (net (code "60") (name "Net-(U1-RXD)") (class "Default")
      (node (ref "R5") (pin "1") (pinfunction "1_1") (pintype "passive"))
      (node (ref "U1") (pin "25") (pinfunction "RXD_25") (pintype "passive"))
    )
    (net (code "61") (name "Net-(U1-SUSPEND)") (class "Default")
      (node (ref "R11") (pin "2") (pinfunction "2_2") (pintype "passive"))
      (node (ref "U1") (pin "12") (pinfunction "SUSPEND_12") (pintype "passive"))
    )
    (net (code "62") (name "Net-(U1-TXD)") (class "Default")
      (node (ref "R4") (pin "1") (pinfunction "1_1") (pintype "passive"))
      (node (ref "U1") (pin "26") (pinfunction "TXD_26") (pintype "passive"))
    )
    (net (code "63") (name "Net-(U1-nRST)") (class "Default")
      (node (ref "R12") (pin "2") (pinfunction "2_2") (pintype "passive"))
      (node (ref "U1") (pin "9") (pinfunction "nRST_9") (pintype "passive"))
    )
    (net (code "64") (name "Net-(U1-nSUSPEND)") (class "Default")
      (node (ref "R10") (pin "2") (pinfunction "2_2") (pintype "passive"))
      (node (ref "U1") (pin "11") (pinfunction "nSUSPEND_11") (pintype "passive"))
    )
    (net (code "65") (name "Net-(U2-PR0)") (class "Default")
      (node (ref "CX1") (pin "2") (pinfunction "2_2") (pintype "passive"))
      (node (ref "U2") (pin "91") (pinfunction "PR0_91") (pintype "passive"))
      (node (ref "Xtal1") (pin "3") (pinfunction "OSC2_3") (pintype "passive"))
    )
    (net (code "66") (name "Net-(U2-PR1)") (class "Default")
      (node (ref "CX2") (pin "2") (pinfunction "2_2") (pintype "passive"))
      (node (ref "U2") (pin "92") (pinfunction "PR1_92") (pintype "passive"))
      (node (ref "Xtal1") (pin "1") (pinfunction "OSC1_1") (pintype "passive"))
    )
    (net (code "67") (name "Net-(U3-AVDD)") (class "Default")
      (node (ref "CB1") (pin "2") (pinfunction "2_2") (pintype "passive"))
      (node (ref "U3") (pin "29") (pinfunction "AVDD_29") (pintype "passive"))
    )
    (net (code "68") (name "Net-(U3-CLKM)") (class "Default")
      (node (ref "R9") (pin "1") (pinfunction "1_1") (pintype "passive"))
      (node (ref "U3") (pin "17") (pinfunction "CLKM_17") (pintype "passive"))
    )
    (net (code "69") (name "Net-(U3-RFN)") (class "Default")
      (node (ref "T1") (pin "3") (pinfunction "BAL_3") (pintype "passive"))
      (node (ref "U3") (pin "5") (pinfunction "RFN_5") (pintype "passive"))
    )
    (net (code "70") (name "Net-(U3-RFP)") (class "Default")
      (node (ref "T1") (pin "4") (pinfunction "BAL_4") (pintype "passive"))
      (node (ref "U3") (pin "4") (pinfunction "RFP_4") (pintype "passive"))
    )
    (net (code "71") (name "Net-(U3-XTAL1)") (class "Default")
      (node (ref "CX4") (pin "2") (pinfunction "2_2") (pintype "passive"))
      (node (ref "U3") (pin "25") (pinfunction "XTAL1_25") (pintype "passive"))
      (node (ref "Xtal2") (pin "3") (pinfunction "OSC2_3") (pintype "passive"))
    )
    (net (code "72") (name "Net-(U3-XTAL2)") (class "Default")
      (node (ref "CX3") (pin "2") (pinfunction "2_2") (pintype "passive"))
      (node (ref "U3") (pin "26") (pinfunction "XTAL2_26") (pintype "passive"))
      (node (ref "Xtal2") (pin "1") (pinfunction "OSC1_1") (pintype "passive"))
    )
    (net (code "73") (name "Net-(U5-IN1)") (class "Default")
      (node (ref "C24") (pin "1") (pinfunction "1_1") (pintype "passive"))
      (node (ref "IC1") (pin "15") (pinfunction "OUT_15") (pintype "output"))
      (node (ref "IC1") (pin "16") (pinfunction "OUT_16") (pintype "output"))
      (node (ref "IC1") (pin "17") (pinfunction "OUT_17") (pintype "output"))
      (node (ref "U5") (pin "3") (pinfunction "IN1_3") (pintype "passive"))
      (node (ref "U5") (pin "4") (pinfunction "IN2_4") (pintype "passive"))
    )
    (net (code "74") (name "Net-(U5-PG)") (class "Default")
      (node (ref "R21") (pin "1") (pinfunction "1_1") (pintype "passive"))
      (node (ref "U5") (pin "8") (pinfunction "PG_8") (pintype "passive"))
    )
    (net (code "75") (name "RF-GND") (class "Default")
      (node (ref "C12") (pin "1") (pinfunction "1_1") (pintype "passive"))
      (node (ref "C26") (pin "1") (pinfunction "1_1") (pintype "passive"))
      (node (ref "CB1") (pin "1") (pinfunction "1_1") (pintype "passive"))
      (node (ref "CB2") (pin "1") (pinfunction "1_1") (pintype "passive"))
      (node (ref "CON1") (pin "3") (pinfunction "GND1_3") (pintype "passive"))
      (node (ref "CON1") (pin "4") (pinfunction "GND2_4") (pintype "passive"))
      (node (ref "CON1") (pin "5") (pinfunction "GND3_5") (pintype "passive"))
      (node (ref "CON1") (pin "6") (pinfunction "GND4_6") (pintype "passive"))
      (node (ref "CX3") (pin "1") (pinfunction "1_1") (pintype "passive"))
      (node (ref "CX4") (pin "1") (pinfunction "1_1") (pintype "passive"))
      (node (ref "L1") (pin "1") (pinfunction "1_1") (pintype "passive"))
      (node (ref "T1") (pin "5") (pinfunction "GND_5") (pintype "passive"))
      (node (ref "T1") (pin "6") (pinfunction "GND_6") (pintype "passive"))
      (node (ref "U3") (pin "1") (pinfunction "AVSS_1") (pintype "passive"))
      (node (ref "U3") (pin "2") (pinfunction "AVSS_2") (pintype "passive"))
      (node (ref "U3") (pin "27") (pinfunction "AVSS_27") (pintype "passive"))
      (node (ref "U3") (pin "3") (pinfunction "AVSS_3") (pintype "passive"))
      (node (ref "U3") (pin "30") (pinfunction "AVSS_30") (pintype "passive"))
      (node (ref "U3") (pin "31") (pinfunction "AVSS_31") (pintype "passive"))
      (node (ref "U3") (pin "32") (pinfunction "AVSS_32") (pintype "passive"))
      (node (ref "U3") (pin "33") (pinfunction "AVSS_33") (pintype "passive"))
      (node (ref "U3") (pin "6") (pinfunction "AVSS_6") (pintype "passive"))
    )
    (net (code "76") (name "RF-VCC") (class "Default")
      (node (ref "C26") (pin "2") (pinfunction "2_2") (pintype "passive"))
      (node (ref "CB2") (pin "2") (pinfunction "2_2") (pintype "passive"))
      (node (ref "L3") (pin "2") (pinfunction "2_2") (pintype "passive"))
      (node (ref "U3") (pin "28") (pinfunction "EVDD_28") (pintype "passive"))
    )
    (net (code "77") (name "U-GND") (class "Default")
      (node (ref "L6") (pin "1") (pinfunction "1_1") (pintype "passive"))
      (node (ref "P4") (pin "ID") (pinfunction "ID_ID") (pintype "passive"))
      (node (ref "P4") (pin "SHIELD") (pinfunction "SHIELD_SHIELD") (pintype "passive"))
      (node (ref "P4") (pin "UGND") (pinfunction "UGND_UGND") (pintype "passive"))
      (node (ref "U4") (pin "1") (pinfunction "GND_1") (pintype "passive"))
    )
    (net (code "78") (name "VCC") (class "Default")
      (node (ref "C1") (pin "1") (pinfunction "1_1") (pintype "passive"))
      (node (ref "C10") (pin "1") (pinfunction "1_1") (pintype "passive"))
      (node (ref "C11") (pin "1") (pinfunction "1_1") (pintype "passive"))
      (node (ref "C13") (pin "1") (pinfunction "1_1") (pintype "passive"))
      (node (ref "C18") (pin "1") (pinfunction "1_1") (pintype "passive"))
      (node (ref "C2") (pin "1") (pinfunction "1_1") (pintype "passive"))
      (node (ref "C23") (pin "1") (pinfunction "1_1") (pintype "passive"))
      (node (ref "C29") (pin "2") (pinfunction "2_2") (pintype "passive"))
      (node (ref "C3") (pin "1") (pinfunction "1_1") (pintype "passive"))
      (node (ref "C30") (pin "2") (pinfunction "2_2") (pintype "passive"))
      (node (ref "C4") (pin "1") (pinfunction "1_1") (pintype "passive"))
      (node (ref "C7") (pin "1") (pinfunction "1_1") (pintype "passive"))
      (node (ref "C8") (pin "1") (pinfunction "1_1") (pintype "passive"))
      (node (ref "C9") (pin "1") (pinfunction "1_1") (pintype "passive"))
      (node (ref "CB4") (pin "1") (pinfunction "1_1") (pintype "passive"))
      (node (ref "F1") (pin "1") (pinfunction "X_1") (pintype "passive"))
      (node (ref "L3") (pin "1") (pinfunction "1_1") (pintype "passive"))
      (node (ref "L4") (pin "1") (pinfunction "1_1") (pintype "passive"))
      (node (ref "P1") (pin "2") (pinfunction "2_2") (pintype "passive"))
      (node (ref "P2") (pin "4") (pinfunction "4_4") (pintype "passive"))
      (node (ref "R1") (pin "2") (pinfunction "2_2") (pintype "passive"))
      (node (ref "R12") (pin "1") (pinfunction "1_1") (pintype "passive"))
      (node (ref "R13") (pin "2") (pinfunction "2_2") (pintype "passive"))
      (node (ref "R14") (pin "2") (pinfunction "2_2") (pintype "passive"))
      (node (ref "R15") (pin "2") (pinfunction "2_2") (pintype "passive"))
      (node (ref "R16") (pin "2") (pinfunction "2_2") (pintype "passive"))
      (node (ref "R17") (pin "2") (pinfunction "2_2") (pintype "passive"))
      (node (ref "R18") (pin "2") (pinfunction "2_2") (pintype "passive"))
      (node (ref "R19") (pin "2") (pinfunction "2_2") (pintype "passive"))
      (node (ref "R21") (pin "2") (pinfunction "2_2") (pintype "passive"))
      (node (ref "R22") (pin "2") (pinfunction "2_2") (pintype "passive"))
      (node (ref "U1") (pin "6") (pinfunction "VDD_6") (pintype "passive"))
      (node (ref "U1") (pin "7") (pinfunction "REGIN_7") (pintype "passive"))
      (node (ref "U2") (pin "14") (pinfunction "VCC_14") (pintype "passive"))
      (node (ref "U2") (pin "24") (pinfunction "VCC_24") (pintype "passive"))
      (node (ref "U2") (pin "34") (pinfunction "VCC_34") (pintype "passive"))
      (node (ref "U2") (pin "44") (pinfunction "VCC_44") (pintype "passive"))
      (node (ref "U2") (pin "54") (pinfunction "VCC_54") (pintype "passive"))
      (node (ref "U2") (pin "64") (pinfunction "VCC_64") (pintype "passive"))
      (node (ref "U2") (pin "74") (pinfunction "VCC_74") (pintype "passive"))
      (node (ref "U2") (pin "83") (pinfunction "VCC_83") (pintype "passive"))
      (node (ref "U3") (pin "15") (pinfunction "DEVDD_15") (pintype "passive"))
      (node (ref "U5") (pin "5") (pinfunction "OUT1_5") (pintype "passive"))
      (node (ref "U5") (pin "6") (pinfunction "OUT2_6") (pintype "passive"))
    )
    (net (code "79") (name "unconnected-(P1-Pad3)") (class "Default")
      (node (ref "P1") (pin "3") (pinfunction "3_3") (pintype "passive"))
    )
    (net (code "80") (name "unconnected-(P1-Pad4)") (class "Default")
      (node (ref "P1") (pin "4") (pinfunction "4_4") (pintype "passive"))
    )
    (net (code "81") (name "unconnected-(P2-Pad7)") (class "Default")
      (node (ref "P2") (pin "7") (pinfunction "7_7") (pintype "passive"))
    )
    (net (code "82") (name "unconnected-(P2-Pad8)") (class "Default")
      (node (ref "P2") (pin "8") (pinfunction "8_8") (pintype "passive"))
    )
    (net (code "83") (name "unconnected-(U1-NC-Pad10)") (class "Default")
      (node (ref "U1") (pin "10") (pinfunction "NC_10") (pintype "passive"))
    )
    (net (code "84") (name "unconnected-(U1-NC-Pad13)") (class "Default")
      (node (ref "U1") (pin "13") (pinfunction "NC_13") (pintype "passive"))
    )
    (net (code "85") (name "unconnected-(U1-NC-Pad14)") (class "Default")
      (node (ref "U1") (pin "14") (pinfunction "NC_14") (pintype "passive"))
    )
    (net (code "86") (name "unconnected-(U1-NC-Pad15)") (class "Default")
      (node (ref "U1") (pin "15") (pinfunction "NC_15") (pintype "passive"))
    )
    (net (code "87") (name "unconnected-(U1-NC-Pad16)") (class "Default")
      (node (ref "U1") (pin "16") (pinfunction "NC_16") (pintype "passive"))
    )
    (net (code "88") (name "unconnected-(U1-NC-Pad17)") (class "Default")
      (node (ref "U1") (pin "17") (pinfunction "NC_17") (pintype "passive"))
    )
    (net (code "89") (name "unconnected-(U1-NC-Pad18)") (class "Default")
      (node (ref "U1") (pin "18") (pinfunction "NC_18") (pintype "passive"))
    )
    (net (code "90") (name "unconnected-(U1-NC-Pad19)") (class "Default")
      (node (ref "U1") (pin "19") (pinfunction "NC_19") (pintype "passive"))
    )
    (net (code "91") (name "unconnected-(U1-NC-Pad20)") (class "Default")
      (node (ref "U1") (pin "20") (pinfunction "NC_20") (pintype "passive"))
    )
    (net (code "92") (name "unconnected-(U1-NC-Pad21)") (class "Default")
      (node (ref "U1") (pin "21") (pinfunction "NC_21") (pintype "passive"))
    )
    (net (code "93") (name "unconnected-(U1-NC-Pad22)") (class "Default")
      (node (ref "U1") (pin "22") (pinfunction "NC_22") (pintype "passive"))
    )
    (net (code "94") (name "unconnected-(U2-PA0-Pad95)") (class "Default")
      (node (ref "U2") (pin "95") (pinfunction "PA0_95") (pintype "passive"))
    )
    (net (code "95") (name "unconnected-(U2-PA1-Pad96)") (class "Default")
      (node (ref "U2") (pin "96") (pinfunction "PA1_96") (pintype "passive"))
    )
    (net (code "96") (name "unconnected-(U2-PA2-Pad97)") (class "Default")
      (node (ref "U2") (pin "97") (pinfunction "PA2_97") (pintype "passive"))
    )
    (net (code "97") (name "unconnected-(U2-PA3-Pad98)") (class "Default")
      (node (ref "U2") (pin "98") (pinfunction "PA3_98") (pintype "passive"))
    )
    (net (code "98") (name "unconnected-(U2-PA4-Pad99)") (class "Default")
      (node (ref "U2") (pin "99") (pinfunction "PA4_99") (pintype "passive"))
    )
    (net (code "99") (name "unconnected-(U2-PA5-Pad100)") (class "Default")
      (node (ref "U2") (pin "100") (pinfunction "PA5_100") (pintype "passive"))
    )
    (net (code "100") (name "unconnected-(U2-PA6-Pad1)") (class "Default")
      (node (ref "U2") (pin "1") (pinfunction "PA6_1") (pintype "passive"))
    )
    (net (code "101") (name "unconnected-(U2-PA7-Pad2)") (class "Default")
      (node (ref "U2") (pin "2") (pinfunction "PA7_2") (pintype "passive"))
    )
    (net (code "102") (name "unconnected-(U2-PB0-Pad5)") (class "Default")
      (node (ref "U2") (pin "5") (pinfunction "PB0_5") (pintype "passive"))
    )
    (net (code "103") (name "unconnected-(U2-PB1-Pad6)") (class "Default")
      (node (ref "U2") (pin "6") (pinfunction "PB1_6") (pintype "passive"))
    )
    (net (code "104") (name "unconnected-(U2-PB2-Pad7)") (class "Default")
      (node (ref "U2") (pin "7") (pinfunction "PB2_7") (pintype "passive"))
    )
    (net (code "105") (name "unconnected-(U2-PB3-Pad8)") (class "Default")
      (node (ref "U2") (pin "8") (pinfunction "PB3_8") (pintype "passive"))
    )
    (net (code "106") (name "unconnected-(U2-PD0-Pad25)") (class "Default")
      (node (ref "U2") (pin "25") (pinfunction "PD0_25") (pintype "passive"))
    )
    (net (code "107") (name "unconnected-(U2-PD1-Pad26)") (class "Default")
      (node (ref "U2") (pin "26") (pinfunction "PD1_26") (pintype "passive"))
    )
    (net (code "108") (name "unconnected-(U2-PD2-Pad27)") (class "Default")
      (node (ref "U2") (pin "27") (pinfunction "PD2_27") (pintype "passive"))
    )
    (net (code "109") (name "unconnected-(U2-PD3-Pad28)") (class "Default")
      (node (ref "U2") (pin "28") (pinfunction "PD3_28") (pintype "passive"))
    )
    (net (code "110") (name "unconnected-(U2-PD4-Pad29)") (class "Default")
      (node (ref "U2") (pin "29") (pinfunction "PD4_29") (pintype "passive"))
    )
    (net (code "111") (name "unconnected-(U2-PD5-Pad30)") (class "Default")
      (node (ref "U2") (pin "30") (pinfunction "PD5_30") (pintype "passive"))
    )
    (net (code "112") (name "unconnected-(U2-PD6-Pad31)") (class "Default")
      (node (ref "U2") (pin "31") (pinfunction "PD6_31") (pintype "passive"))
    )
    (net (code "113") (name "unconnected-(U2-PD7-Pad32)") (class "Default")
      (node (ref "U2") (pin "32") (pinfunction "PD7_32") (pintype "passive"))
    )
    (net (code "114") (name "unconnected-(U2-PE0-Pad35)") (class "Default")
      (node (ref "U2") (pin "35") (pinfunction "PE0_35") (pintype "passive"))
    )
    (net (code "115") (name "unconnected-(U2-PE1-Pad36)") (class "Default")
      (node (ref "U2") (pin "36") (pinfunction "PE1_36") (pintype "passive"))
    )
    (net (code "116") (name "unconnected-(U2-PE2-Pad37)") (class "Default")
      (node (ref "U2") (pin "37") (pinfunction "PE2_37") (pintype "passive"))
    )
    (net (code "117") (name "unconnected-(U2-PE3-Pad38)") (class "Default")
      (node (ref "U2") (pin "38") (pinfunction "PE3_38") (pintype "passive"))
    )
    (net (code "118") (name "unconnected-(U2-PE4-Pad39)") (class "Default")
      (node (ref "U2") (pin "39") (pinfunction "PE4_39") (pintype "passive"))
    )
    (net (code "119") (name "unconnected-(U2-PE5-Pad40)") (class "Default")
      (node (ref "U2") (pin "40") (pinfunction "PE5_40") (pintype "passive"))
    )
    (net (code "120") (name "unconnected-(U2-PE6-Pad41)") (class "Default")
      (node (ref "U2") (pin "41") (pinfunction "PE6_41") (pintype "passive"))
    )
    (net (code "121") (name "unconnected-(U2-PE7-Pad42)") (class "Default")
      (node (ref "U2") (pin "42") (pinfunction "PE7_42") (pintype "passive"))
    )
    (net (code "122") (name "unconnected-(U2-PF0-Pad45)") (class "Default")
      (node (ref "U2") (pin "45") (pinfunction "PF0_45") (pintype "passive"))
    )
    (net (code "123") (name "unconnected-(U2-PH0-Pad55)") (class "Default")
      (node (ref "U2") (pin "55") (pinfunction "PH0_55") (pintype "passive"))
    )
    (net (code "124") (name "unconnected-(U2-PH1-Pad56)") (class "Default")
      (node (ref "U2") (pin "56") (pinfunction "PH1_56") (pintype "passive"))
    )
    (net (code "125") (name "unconnected-(U2-PH2-Pad57)") (class "Default")
      (node (ref "U2") (pin "57") (pinfunction "PH2_57") (pintype "passive"))
    )
    (net (code "126") (name "unconnected-(U2-PH3-Pad58)") (class "Default")
      (node (ref "U2") (pin "58") (pinfunction "PH3_58") (pintype "passive"))
    )
    (net (code "127") (name "unconnected-(U2-PH4-Pad59)") (class "Default")
      (node (ref "U2") (pin "59") (pinfunction "PH4_59") (pintype "passive"))
    )
    (net (code "128") (name "unconnected-(U2-PH5-Pad60)") (class "Default")
      (node (ref "U2") (pin "60") (pinfunction "PH5_60") (pintype "passive"))
    )
    (net (code "129") (name "unconnected-(U2-PH6-Pad61)") (class "Default")
      (node (ref "U2") (pin "61") (pinfunction "PH6_61") (pintype "passive"))
    )
    (net (code "130") (name "unconnected-(U2-PH7-Pad62)") (class "Default")
      (node (ref "U2") (pin "62") (pinfunction "PH7_62") (pintype "passive"))
    )
    (net (code "131") (name "unconnected-(U2-PJ0-Pad65)") (class "Default")
      (node (ref "U2") (pin "65") (pinfunction "PJ0_65") (pintype "passive"))
    )
    (net (code "132") (name "unconnected-(U2-PJ1-Pad66)") (class "Default")
      (node (ref "U2") (pin "66") (pinfunction "PJ1_66") (pintype "passive"))
    )
    (net (code "133") (name "unconnected-(U2-PJ2-Pad67)") (class "Default")
      (node (ref "U2") (pin "67") (pinfunction "PJ2_67") (pintype "passive"))
    )
    (net (code "134") (name "unconnected-(U2-PJ3-Pad68)") (class "Default")
      (node (ref "U2") (pin "68") (pinfunction "PJ3_68") (pintype "passive"))
    )
    (net (code "135") (name "unconnected-(U2-PJ4-Pad69)") (class "Default")
      (node (ref "U2") (pin "69") (pinfunction "PJ4_69") (pintype "passive"))
    )
    (net (code "136") (name "unconnected-(U2-PJ5-Pad70)") (class "Default")
      (node (ref "U2") (pin "70") (pinfunction "PJ5_70") (pintype "passive"))
    )
    (net (code "137") (name "unconnected-(U2-PJ6-Pad71)") (class "Default")
      (node (ref "U2") (pin "71") (pinfunction "PJ6_71") (pintype "passive"))
    )
    (net (code "138") (name "unconnected-(U2-PJ7-Pad72)") (class "Default")
      (node (ref "U2") (pin "72") (pinfunction "PJ7_72") (pintype "passive"))
    )
    (net (code "139") (name "unconnected-(U2-PK0-Pad75)") (class "Default")
      (node (ref "U2") (pin "75") (pinfunction "PK0_75") (pintype "passive"))
    )
    (net (code "140") (name "unconnected-(U2-PK1-Pad76)") (class "Default")
      (node (ref "U2") (pin "76") (pinfunction "PK1_76") (pintype "passive"))
    )
    (net (code "141") (name "unconnected-(U2-PK2-Pad77)") (class "Default")
      (node (ref "U2") (pin "77") (pinfunction "PK2_77") (pintype "passive"))
    )
    (net (code "142") (name "unconnected-(U2-PK3-Pad78)") (class "Default")
      (node (ref "U2") (pin "78") (pinfunction "PK3_78") (pintype "passive"))
    )
    (net (code "143") (name "unconnected-(U2-PK4-Pad79)") (class "Default")
      (node (ref "U2") (pin "79") (pinfunction "PK4_79") (pintype "passive"))
    )
    (net (code "144") (name "unconnected-(U2-PK5-Pad80)") (class "Default")
      (node (ref "U2") (pin "80") (pinfunction "PK5_80") (pintype "passive"))
    )
    (net (code "145") (name "unconnected-(U2-PK6-Pad81)") (class "Default")
      (node (ref "U2") (pin "81") (pinfunction "PK6_81") (pintype "passive"))
    )
    (net (code "146") (name "unconnected-(U2-PK7-Pad82)") (class "Default")
      (node (ref "U2") (pin "82") (pinfunction "PK7_82") (pintype "passive"))
    )
    (net (code "147") (name "unconnected-(U2-PQ0-Pad85)") (class "Default")
      (node (ref "U2") (pin "85") (pinfunction "PQ0_85") (pintype "passive"))
    )
    (net (code "148") (name "unconnected-(U2-PQ1-Pad86)") (class "Default")
      (node (ref "U2") (pin "86") (pinfunction "PQ1_86") (pintype "passive"))
    )
    (net (code "149") (name "unconnected-(U2-PQ2-Pad87)") (class "Default")
      (node (ref "U2") (pin "87") (pinfunction "PQ2_87") (pintype "passive"))
    )
    (net (code "150") (name "unconnected-(U2-PQ3-Pad88)") (class "Default")
      (node (ref "U2") (pin "88") (pinfunction "PQ3_88") (pintype "passive"))
    )
    (net (code "151") (name "unconnected-(U5-FB-Pad7)") (class "Default")
      (node (ref "U5") (pin "7") (pinfunction "FB_7") (pintype "passive"))
    )
    (net (code "152") (name "unconnected-(Xtal1-OSC2-Pad2)") (class "Default")
      (node (ref "Xtal1") (pin "2") (pinfunction "OSC2_2") (pintype "passive"))
    )
    (net (code "153") (name "unconnected-(Xtal1-OSC2-Pad4)") (class "Default")
      (node (ref "Xtal1") (pin "4") (pinfunction "OSC2_4") (pintype "passive"))
    )
    (net (code "154") (name "unconnected-(Xtal2-OSC2-Pad2)") (class "Default")
      (node (ref "Xtal2") (pin "2") (pinfunction "OSC2_2") (pintype "passive"))
    )
    (net (code "155") (name "unconnected-(Xtal2-OSC2-Pad4)") (class "Default")
      (node (ref "Xtal2") (pin "4") (pinfunction "OSC2_4") (pintype "passive"))
    )
  )
)
